# KYBRDv2.net
KiCad netlist of a schematic drawn in EAGLE
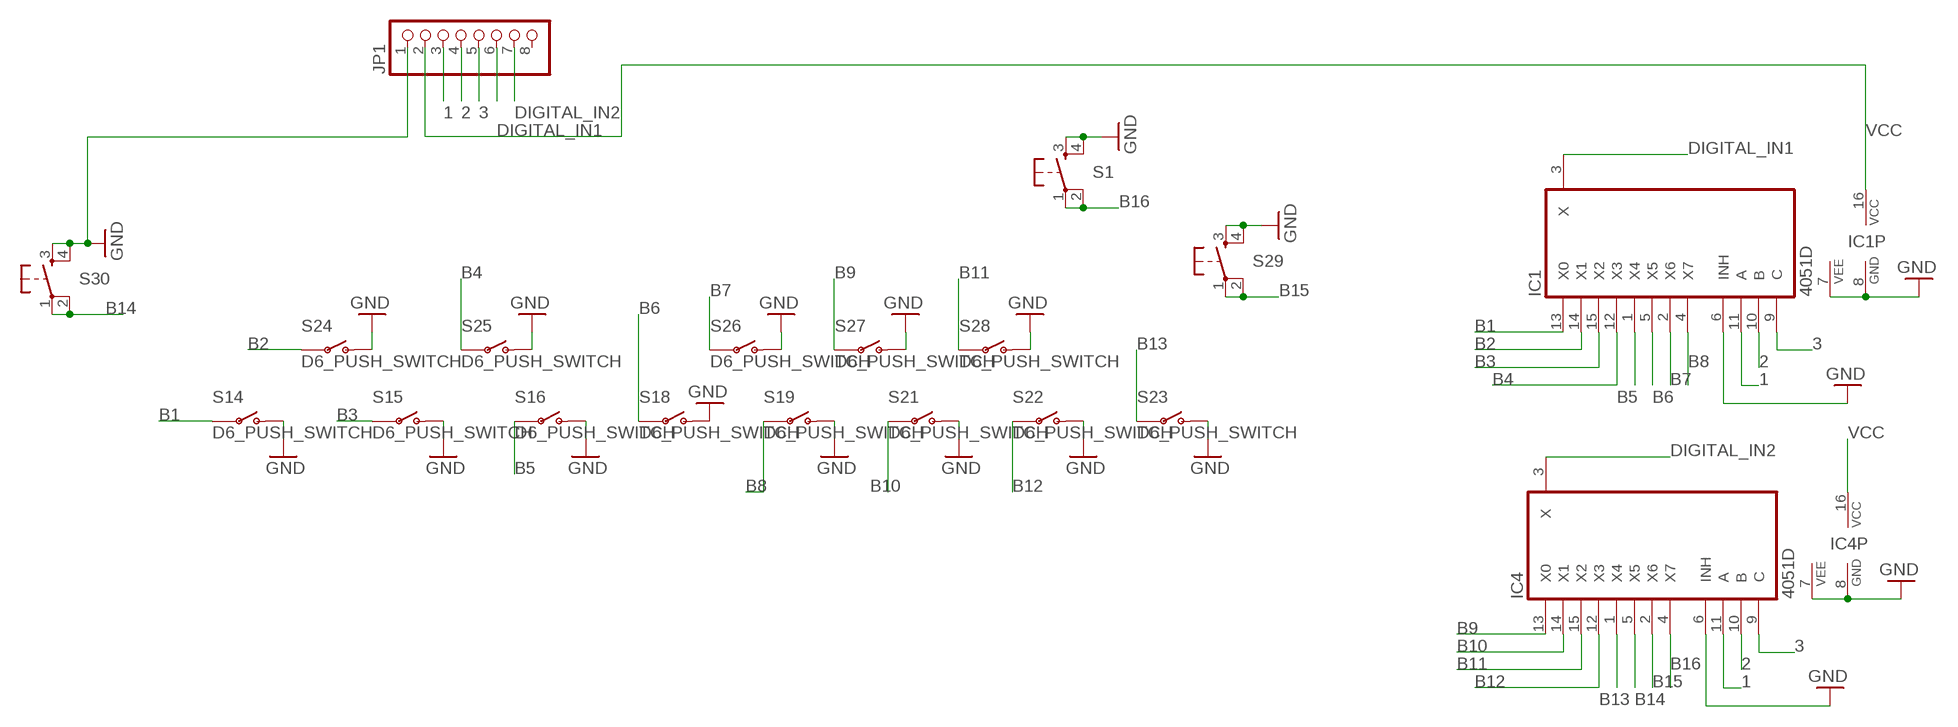
[diagram p0: schematic, sheet 1]

(export (version "E")
  (design (tool "Eeschema 10.0.6"))
  (components
    (comp (ref "IC1")
      (value "4051D")
      (footprint "eagle-import:SO16")
      (libsource (lib "eagle-import") (part "4051D"))
    )
    (comp (ref "IC4")
      (value "4051D")
      (footprint "eagle-import:SO16")
      (libsource (lib "eagle-import") (part "4051D"))
    )
    (comp (ref "JP1")
      (value "PINHD-1X8")
      (footprint "eagle-import:1X08")
      (libsource (lib "eagle-import") (part "PINHD-1X8"))
    )
    (comp (ref "S1")
      (value "DTSM-6")
      (footprint "eagle-import:DTSM-6")
      (libsource (lib "eagle-import") (part "DTSM-6"))
    )
    (comp (ref "S14")
      (value "D6_PUSH_SWITCH")
      (footprint "eagle-import:D6_PUSH_SWITCH")
      (libsource (lib "eagle-import") (part "D6_PUSH_SWITCH"))
    )
    (comp (ref "S15")
      (value "D6_PUSH_SWITCH")
      (footprint "eagle-import:D6_PUSH_SWITCH")
      (libsource (lib "eagle-import") (part "D6_PUSH_SWITCH"))
    )
    (comp (ref "S16")
      (value "D6_PUSH_SWITCH")
      (footprint "eagle-import:D6_PUSH_SWITCH")
      (libsource (lib "eagle-import") (part "D6_PUSH_SWITCH"))
    )
    (comp (ref "S18")
      (value "D6_PUSH_SWITCH")
      (footprint "eagle-import:D6_PUSH_SWITCH")
      (libsource (lib "eagle-import") (part "D6_PUSH_SWITCH"))
    )
    (comp (ref "S19")
      (value "D6_PUSH_SWITCH")
      (footprint "eagle-import:D6_PUSH_SWITCH")
      (libsource (lib "eagle-import") (part "D6_PUSH_SWITCH"))
    )
    (comp (ref "S21")
      (value "D6_PUSH_SWITCH")
      (footprint "eagle-import:D6_PUSH_SWITCH")
      (libsource (lib "eagle-import") (part "D6_PUSH_SWITCH"))
    )
    (comp (ref "S22")
      (value "D6_PUSH_SWITCH")
      (footprint "eagle-import:D6_PUSH_SWITCH")
      (libsource (lib "eagle-import") (part "D6_PUSH_SWITCH"))
    )
    (comp (ref "S23")
      (value "D6_PUSH_SWITCH")
      (footprint "eagle-import:D6_PUSH_SWITCH")
      (libsource (lib "eagle-import") (part "D6_PUSH_SWITCH"))
    )
    (comp (ref "S24")
      (value "D6_PUSH_SWITCH")
      (footprint "eagle-import:D6_PUSH_SWITCH")
      (libsource (lib "eagle-import") (part "D6_PUSH_SWITCH"))
    )
    (comp (ref "S25")
      (value "D6_PUSH_SWITCH")
      (footprint "eagle-import:D6_PUSH_SWITCH")
      (libsource (lib "eagle-import") (part "D6_PUSH_SWITCH"))
    )
    (comp (ref "S26")
      (value "D6_PUSH_SWITCH")
      (footprint "eagle-import:D6_PUSH_SWITCH")
      (libsource (lib "eagle-import") (part "D6_PUSH_SWITCH"))
    )
    (comp (ref "S27")
      (value "D6_PUSH_SWITCH")
      (footprint "eagle-import:D6_PUSH_SWITCH")
      (libsource (lib "eagle-import") (part "D6_PUSH_SWITCH"))
    )
    (comp (ref "S28")
      (value "D6_PUSH_SWITCH")
      (footprint "eagle-import:D6_PUSH_SWITCH")
      (libsource (lib "eagle-import") (part "D6_PUSH_SWITCH"))
    )
    (comp (ref "S29")
      (value "DTSM-6")
      (footprint "eagle-import:DTSM-6")
      (libsource (lib "eagle-import") (part "DTSM-6"))
    )
    (comp (ref "S30")
      (value "DTSM-6")
      (footprint "eagle-import:DTSM-6")
      (libsource (lib "eagle-import") (part "DTSM-6"))
    )
  )
  (nets
    (net (code "1") (name "/1") (class "Default")
      (node (ref "IC1") (pin "11") (pinfunction "A_11") (pintype "input"))
      (node (ref "IC4") (pin "11") (pinfunction "A_11") (pintype "input"))
      (node (ref "JP1") (pin "3") (pinfunction "3_3") (pintype "passive"))
    )
    (net (code "2") (name "/2") (class "Default")
      (node (ref "IC1") (pin "10") (pinfunction "B_10") (pintype "input"))
      (node (ref "IC4") (pin "10") (pinfunction "B_10") (pintype "input"))
      (node (ref "JP1") (pin "4") (pinfunction "4_4") (pintype "passive"))
    )
    (net (code "3") (name "/3") (class "Default")
      (node (ref "IC1") (pin "9") (pinfunction "C_9") (pintype "input"))
      (node (ref "IC4") (pin "9") (pinfunction "C_9") (pintype "input"))
      (node (ref "JP1") (pin "5") (pinfunction "5_5") (pintype "passive"))
    )
    (net (code "4") (name "/B1") (class "Default")
      (node (ref "IC1") (pin "13") (pinfunction "X0_13") (pintype "bidirectional"))
      (node (ref "S14") (pin "P$3") (pinfunction "P_P$3") (pintype "passive"))
      (node (ref "S14") (pin "P$4") (pinfunction "P_P$4") (pintype "passive"))
    )
    (net (code "5") (name "/B2") (class "Default")
      (node (ref "IC1") (pin "14") (pinfunction "X1_14") (pintype "bidirectional"))
      (node (ref "S24") (pin "P$3") (pinfunction "P_P$3") (pintype "passive"))
      (node (ref "S24") (pin "P$4") (pinfunction "P_P$4") (pintype "passive"))
    )
    (net (code "6") (name "/B3") (class "Default")
      (node (ref "IC1") (pin "15") (pinfunction "X2_15") (pintype "bidirectional"))
      (node (ref "S15") (pin "P$3") (pinfunction "P_P$3") (pintype "passive"))
      (node (ref "S15") (pin "P$4") (pinfunction "P_P$4") (pintype "passive"))
    )
    (net (code "7") (name "/B4") (class "Default")
      (node (ref "IC1") (pin "12") (pinfunction "X3_12") (pintype "bidirectional"))
      (node (ref "S25") (pin "P$3") (pinfunction "P_P$3") (pintype "passive"))
      (node (ref "S25") (pin "P$4") (pinfunction "P_P$4") (pintype "passive"))
    )
    (net (code "8") (name "/B5") (class "Default")
      (node (ref "IC1") (pin "1") (pinfunction "X4_1") (pintype "bidirectional"))
      (node (ref "S16") (pin "P$3") (pinfunction "P_P$3") (pintype "passive"))
      (node (ref "S16") (pin "P$4") (pinfunction "P_P$4") (pintype "passive"))
    )
    (net (code "9") (name "/B6") (class "Default")
      (node (ref "IC1") (pin "5") (pinfunction "X5_5") (pintype "bidirectional"))
      (node (ref "S18") (pin "P$3") (pinfunction "P_P$3") (pintype "passive"))
      (node (ref "S18") (pin "P$4") (pinfunction "P_P$4") (pintype "passive"))
    )
    (net (code "10") (name "/B7") (class "Default")
      (node (ref "IC1") (pin "2") (pinfunction "X6_2") (pintype "bidirectional"))
      (node (ref "S26") (pin "P$3") (pinfunction "P_P$3") (pintype "passive"))
      (node (ref "S26") (pin "P$4") (pinfunction "P_P$4") (pintype "passive"))
    )
    (net (code "11") (name "/B8") (class "Default")
      (node (ref "IC1") (pin "4") (pinfunction "X7_4") (pintype "bidirectional"))
      (node (ref "S19") (pin "P$3") (pinfunction "P_P$3") (pintype "passive"))
      (node (ref "S19") (pin "P$4") (pinfunction "P_P$4") (pintype "passive"))
    )
    (net (code "12") (name "/B9") (class "Default")
      (node (ref "IC4") (pin "13") (pinfunction "X0_13") (pintype "bidirectional"))
      (node (ref "S27") (pin "P$3") (pinfunction "P_P$3") (pintype "passive"))
      (node (ref "S27") (pin "P$4") (pinfunction "P_P$4") (pintype "passive"))
    )
    (net (code "13") (name "/B10") (class "Default")
      (node (ref "IC4") (pin "14") (pinfunction "X1_14") (pintype "bidirectional"))
      (node (ref "S21") (pin "P$3") (pinfunction "P_P$3") (pintype "passive"))
      (node (ref "S21") (pin "P$4") (pinfunction "P_P$4") (pintype "passive"))
    )
    (net (code "14") (name "/B11") (class "Default")
      (node (ref "IC4") (pin "15") (pinfunction "X2_15") (pintype "bidirectional"))
      (node (ref "S28") (pin "P$3") (pinfunction "P_P$3") (pintype "passive"))
      (node (ref "S28") (pin "P$4") (pinfunction "P_P$4") (pintype "passive"))
    )
    (net (code "15") (name "/B12") (class "Default")
      (node (ref "IC4") (pin "12") (pinfunction "X3_12") (pintype "bidirectional"))
      (node (ref "S22") (pin "P$3") (pinfunction "P_P$3") (pintype "passive"))
      (node (ref "S22") (pin "P$4") (pinfunction "P_P$4") (pintype "passive"))
    )
    (net (code "16") (name "/B13") (class "Default")
      (node (ref "IC4") (pin "1") (pinfunction "X4_1") (pintype "bidirectional"))
      (node (ref "S23") (pin "P$3") (pinfunction "P_P$3") (pintype "passive"))
      (node (ref "S23") (pin "P$4") (pinfunction "P_P$4") (pintype "passive"))
    )
    (net (code "17") (name "/B14") (class "Default")
      (node (ref "IC4") (pin "5") (pinfunction "X5_5") (pintype "bidirectional"))
      (node (ref "S30") (pin "1") (pinfunction "1_1") (pintype "passive"))
      (node (ref "S30") (pin "2") (pinfunction "2_2") (pintype "passive"))
    )
    (net (code "18") (name "/B15") (class "Default")
      (node (ref "IC4") (pin "2") (pinfunction "X6_2") (pintype "bidirectional"))
      (node (ref "S29") (pin "1") (pinfunction "1_1") (pintype "passive"))
      (node (ref "S29") (pin "2") (pinfunction "2_2") (pintype "passive"))
    )
    (net (code "19") (name "/B16") (class "Default")
      (node (ref "IC4") (pin "4") (pinfunction "X7_4") (pintype "bidirectional"))
      (node (ref "S1") (pin "1") (pinfunction "1_1") (pintype "passive"))
      (node (ref "S1") (pin "2") (pinfunction "2_2") (pintype "passive"))
    )
    (net (code "20") (name "/DIGITAL_IN1") (class "Default")
      (node (ref "IC1") (pin "3") (pinfunction "X_3") (pintype "bidirectional"))
      (node (ref "JP1") (pin "6") (pinfunction "6_6") (pintype "passive"))
    )
    (net (code "21") (name "/DIGITAL_IN2") (class "Default")
      (node (ref "IC4") (pin "3") (pinfunction "X_3") (pintype "bidirectional"))
      (node (ref "JP1") (pin "7") (pinfunction "7_7") (pintype "passive"))
    )
    (net (code "22") (name "/VCC") (class "Default")
      (node (ref "IC1") (pin "16") (pinfunction "VCC_16") (pintype "power_in"))
      (node (ref "IC4") (pin "16") (pinfunction "VCC_16") (pintype "power_in"))
      (node (ref "JP1") (pin "2") (pinfunction "2_2") (pintype "passive"))
    )
    (net (code "23") (name "GND") (class "Default")
      (node (ref "IC1") (pin "6") (pinfunction "INH_6") (pintype "input"))
      (node (ref "IC1") (pin "7") (pinfunction "VEE_7") (pintype "power_in"))
      (node (ref "IC1") (pin "8") (pinfunction "GND_8") (pintype "power_in"))
      (node (ref "IC4") (pin "6") (pinfunction "INH_6") (pintype "input"))
      (node (ref "IC4") (pin "7") (pinfunction "VEE_7") (pintype "power_in"))
      (node (ref "IC4") (pin "8") (pinfunction "GND_8") (pintype "power_in"))
      (node (ref "JP1") (pin "1") (pinfunction "1_1") (pintype "passive"))
      (node (ref "S1") (pin "3") (pinfunction "3_3") (pintype "passive"))
      (node (ref "S1") (pin "4") (pinfunction "4_4") (pintype "passive"))
      (node (ref "S14") (pin "P$1") (pinfunction "O_P$1") (pintype "passive"))
      (node (ref "S14") (pin "P$2") (pinfunction "O_P$2") (pintype "passive"))
      (node (ref "S15") (pin "P$1") (pinfunction "O_P$1") (pintype "passive"))
      (node (ref "S15") (pin "P$2") (pinfunction "O_P$2") (pintype "passive"))
      (node (ref "S16") (pin "P$1") (pinfunction "O_P$1") (pintype "passive"))
      (node (ref "S16") (pin "P$2") (pinfunction "O_P$2") (pintype "passive"))
      (node (ref "S18") (pin "P$1") (pinfunction "O_P$1") (pintype "passive"))
      (node (ref "S18") (pin "P$2") (pinfunction "O_P$2") (pintype "passive"))
      (node (ref "S19") (pin "P$1") (pinfunction "O_P$1") (pintype "passive"))
      (node (ref "S19") (pin "P$2") (pinfunction "O_P$2") (pintype "passive"))
      (node (ref "S21") (pin "P$1") (pinfunction "O_P$1") (pintype "passive"))
      (node (ref "S21") (pin "P$2") (pinfunction "O_P$2") (pintype "passive"))
      (node (ref "S22") (pin "P$1") (pinfunction "O_P$1") (pintype "passive"))
      (node (ref "S22") (pin "P$2") (pinfunction "O_P$2") (pintype "passive"))
      (node (ref "S23") (pin "P$1") (pinfunction "O_P$1") (pintype "passive"))
      (node (ref "S23") (pin "P$2") (pinfunction "O_P$2") (pintype "passive"))
      (node (ref "S24") (pin "P$1") (pinfunction "O_P$1") (pintype "passive"))
      (node (ref "S24") (pin "P$2") (pinfunction "O_P$2") (pintype "passive"))
      (node (ref "S25") (pin "P$1") (pinfunction "O_P$1") (pintype "passive"))
      (node (ref "S25") (pin "P$2") (pinfunction "O_P$2") (pintype "passive"))
      (node (ref "S26") (pin "P$1") (pinfunction "O_P$1") (pintype "passive"))
      (node (ref "S26") (pin "P$2") (pinfunction "O_P$2") (pintype "passive"))
      (node (ref "S27") (pin "P$1") (pinfunction "O_P$1") (pintype "passive"))
      (node (ref "S27") (pin "P$2") (pinfunction "O_P$2") (pintype "passive"))
      (node (ref "S28") (pin "P$1") (pinfunction "O_P$1") (pintype "passive"))
      (node (ref "S28") (pin "P$2") (pinfunction "O_P$2") (pintype "passive"))
      (node (ref "S29") (pin "3") (pinfunction "3_3") (pintype "passive"))
      (node (ref "S29") (pin "4") (pinfunction "4_4") (pintype "passive"))
      (node (ref "S30") (pin "3") (pinfunction "3_3") (pintype "passive"))
      (node (ref "S30") (pin "4") (pinfunction "4_4") (pintype "passive"))
    )
    (net (code "24") (name "unconnected-(JP1-Pad8)") (class "Default")
      (node (ref "JP1") (pin "8") (pinfunction "8_8") (pintype "passive"))
    )
  )
)
